# comunicacao.net
KiCad netlist of a schematic drawn in Altium Designer
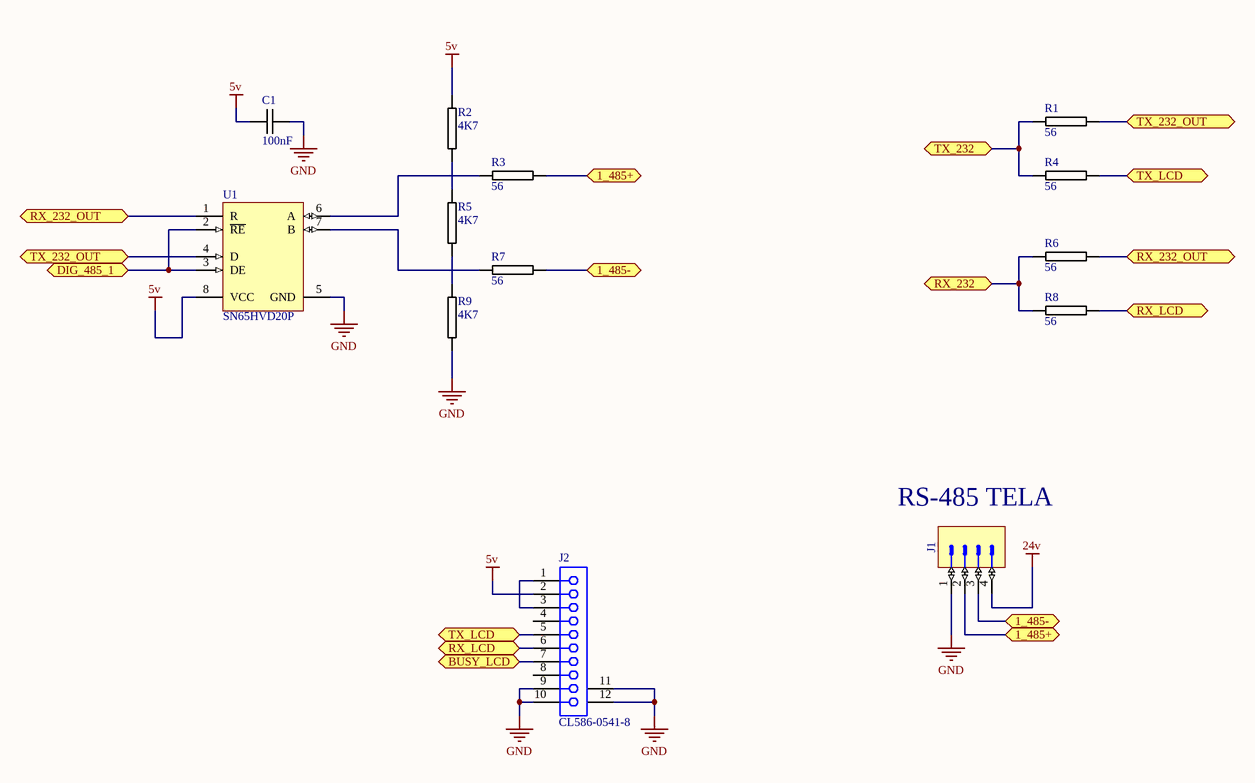
[diagram p0: comunicacao.SchDoc]

(export (version "E")
  (design (tool "Eeschema 10.0.6"))
  (components
    (comp (ref "C1")
      (value "100nF")
      (footprint "0805C-TBD")
      (description "CAPACITOR 0805 CERAMIC")
      (libsource (lib "vh_altium_library") (part "0805C-100nF-25V-X7R-MUR"))
    )
    (comp (ref "J1")
      (value "~")
      (footprint "PHOENIX_1757268")
      (description "Connector 4 Male")
      (fields
        (field (name "PART NUMBER") "PHOENIX_1757268")
        (field (name "MANUFACTURER") "PHOENIX CONTACT")
        (field (name "AUTHOR") "CERN DEM JLC")
      )
      (libsource (lib "Connectors") (part "Connector 4 Male"))
    )
    (comp (ref "J2")
      (value "CL586-0541-8")
      (footprint "FH12-22(10)SA-1SH")
      (description "FH12 Series, \"Flip-Lock\" SMT/ZIF FFC/FPC Connector - 1.0mm Spaced Bottom Eccentric Contact")
      (fields (field (name "PUBLISHER") "Altium Limited"))
      (libsource (lib "HRS FPC-FFC FH12 Series") (part "CL586-0541-8"))
    )
    (comp (ref "R1")
      (value "56")
      (footprint "0805R-56")
      (description "RESISTOR 0805 1/4 WATT THIN FILM")
      (libsource (lib "vh_altium_library") (part "0805R-56"))
    )
    (comp (ref "R2")
      (value "4K7")
      (footprint "0805R-4K7")
      (description "RESISTOR 0805 1/4 WATT THIN FILM")
      (libsource (lib "vh_altium_library") (part "0805R-4K7"))
    )
    (comp (ref "R3")
      (value "56")
      (footprint "0805R-56")
      (description "RESISTOR 0805 1/4 WATT THIN FILM")
      (libsource (lib "vh_altium_library") (part "0805R-56"))
    )
    (comp (ref "R4")
      (value "56")
      (footprint "0805R-56")
      (description "RESISTOR 0805 1/4 WATT THIN FILM")
      (libsource (lib "vh_altium_library") (part "0805R-56"))
    )
    (comp (ref "R5")
      (value "4K7")
      (footprint "0805R-4K7")
      (description "RESISTOR 0805 1/4 WATT THIN FILM")
      (libsource (lib "vh_altium_library") (part "0805R-4K7"))
    )
    (comp (ref "R6")
      (value "56")
      (footprint "0805R-56")
      (description "RESISTOR 0805 1/4 WATT THIN FILM")
      (libsource (lib "vh_altium_library") (part "0805R-56"))
    )
    (comp (ref "R7")
      (value "56")
      (footprint "0805R-56")
      (description "RESISTOR 0805 1/4 WATT THIN FILM")
      (libsource (lib "vh_altium_library") (part "0805R-56"))
    )
    (comp (ref "R8")
      (value "56")
      (footprint "0805R-56")
      (description "RESISTOR 0805 1/4 WATT THIN FILM")
      (libsource (lib "vh_altium_library") (part "0805R-56"))
    )
    (comp (ref "R9")
      (value "4K7")
      (footprint "0805R-4K7")
      (description "RESISTOR 0805 1/4 WATT THIN FILM")
      (libsource (lib "vh_altium_library") (part "0805R-4K7"))
    )
    (comp (ref "U1")
      (value "SN65HVD20P")
      (footprint "P8")
      (fields (field (name "MANUFACTURER") "Texas Instruments"))
      (libsource (lib "Texas Instruments Interface RS-485") (part "SN65HVD20P"))
    )
  )
  (nets
    (net (code "1") (name "/1_485+") (class "Default")
      (node (ref "J1") (pin "2") (pinfunction "2_2") (pintype "bidirectional"))
      (node (ref "R3") (pin "2") (pintype "passive"))
    )
    (net (code "2") (name "/1_485-") (class "Default")
      (node (ref "J1") (pin "3") (pinfunction "3_3") (pintype "bidirectional"))
      (node (ref "R7") (pin "2") (pintype "passive"))
    )
    (net (code "3") (name "/BUSY_LCD") (class "Default")
      (node (ref "J2") (pin "7") (pinfunction "7_7") (pintype "passive"))
    )
    (net (code "4") (name "/DIG_485_1") (class "Default")
      (node (ref "U1") (pin "2") (pinfunction "~{RE}_2") (pintype "input"))
      (node (ref "U1") (pin "3") (pinfunction "DE_3") (pintype "input"))
    )
    (net (code "5") (name "/RX_232") (class "Default")
      (node (ref "R6") (pin "1") (pintype "passive"))
      (node (ref "R8") (pin "1") (pintype "passive"))
    )
    (net (code "6") (name "/RX_232_OUT") (class "Default")
      (node (ref "R6") (pin "2") (pintype "passive"))
      (node (ref "U1") (pin "1") (pinfunction "R_1") (pintype "tri_state"))
    )
    (net (code "7") (name "/RX_LCD") (class "Default")
      (node (ref "J2") (pin "6") (pinfunction "6_6") (pintype "passive"))
      (node (ref "R8") (pin "2") (pintype "passive"))
    )
    (net (code "8") (name "/TX_232") (class "Default")
      (node (ref "R1") (pin "1") (pintype "passive"))
      (node (ref "R4") (pin "1") (pintype "passive"))
    )
    (net (code "9") (name "/TX_232_OUT") (class "Default")
      (node (ref "R1") (pin "2") (pintype "passive"))
      (node (ref "U1") (pin "4") (pinfunction "D_4") (pintype "input"))
    )
    (net (code "10") (name "/TX_LCD") (class "Default")
      (node (ref "J2") (pin "5") (pinfunction "5_5") (pintype "passive"))
      (node (ref "R4") (pin "2") (pintype "passive"))
    )
    (net (code "11") (name "5v") (class "Default")
      (node (ref "C1") (pin "1") (pintype "passive"))
      (node (ref "J2") (pin "2") (pinfunction "2_2") (pintype "passive"))
      (node (ref "R2") (pin "1") (pintype "passive"))
      (node (ref "U1") (pin "8") (pinfunction "VCC_8") (pintype "power_in"))
    )
    (net (code "12") (name "24v") (class "Default")
      (node (ref "J1") (pin "4") (pinfunction "4_4") (pintype "bidirectional"))
    )
    (net (code "13") (name "GND") (class "Default")
      (node (ref "C1") (pin "2") (pintype "passive"))
      (node (ref "J1") (pin "1") (pinfunction "1_1") (pintype "bidirectional"))
      (node (ref "J2") (pin "10") (pinfunction "10_10") (pintype "passive"))
      (node (ref "J2") (pin "11") (pinfunction "MH1_11") (pintype "passive"))
      (node (ref "J2") (pin "12") (pinfunction "MH2_12") (pintype "passive"))
      (node (ref "J2") (pin "9") (pinfunction "9_9") (pintype "passive"))
      (node (ref "R9") (pin "2") (pintype "passive"))
      (node (ref "U1") (pin "5") (pinfunction "GND_5") (pintype "power_in"))
    )
    (net (code "14") (name "Net-(J2-Pad1)") (class "Default")
      (node (ref "J2") (pin "1") (pinfunction "1_1") (pintype "passive"))
      (node (ref "J2") (pin "3") (pinfunction "3_3") (pintype "passive"))
    )
    (net (code "15") (name "Net-(R2-Pad2)") (class "Default")
      (node (ref "R2") (pin "2") (pintype "passive"))
      (node (ref "R5") (pin "1") (pintype "passive"))
    )
    (net (code "16") (name "Net-(R5-Pad2)") (class "Default")
      (node (ref "R5") (pin "2") (pintype "passive"))
      (node (ref "R9") (pin "1") (pintype "passive"))
    )
    (net (code "17") (name "Net-(U1-A)") (class "Default")
      (node (ref "R3") (pin "1") (pintype "passive"))
      (node (ref "U1") (pin "6") (pinfunction "A_6") (pintype "bidirectional"))
    )
    (net (code "18") (name "Net-(U1-B)") (class "Default")
      (node (ref "R7") (pin "1") (pintype "passive"))
      (node (ref "U1") (pin "7") (pinfunction "B_7") (pintype "bidirectional"))
    )
    (net (code "19") (name "unconnected-(J2-Pad4)") (class "Default")
      (node (ref "J2") (pin "4") (pinfunction "4_4") (pintype "passive"))
    )
    (net (code "20") (name "unconnected-(J2-Pad8)") (class "Default")
      (node (ref "J2") (pin "8") (pinfunction "8_8") (pintype "passive"))
    )
  )
)
